# CON_SPDIF_IN.net
KiCad netlist of a schematic drawn in Altium Designer
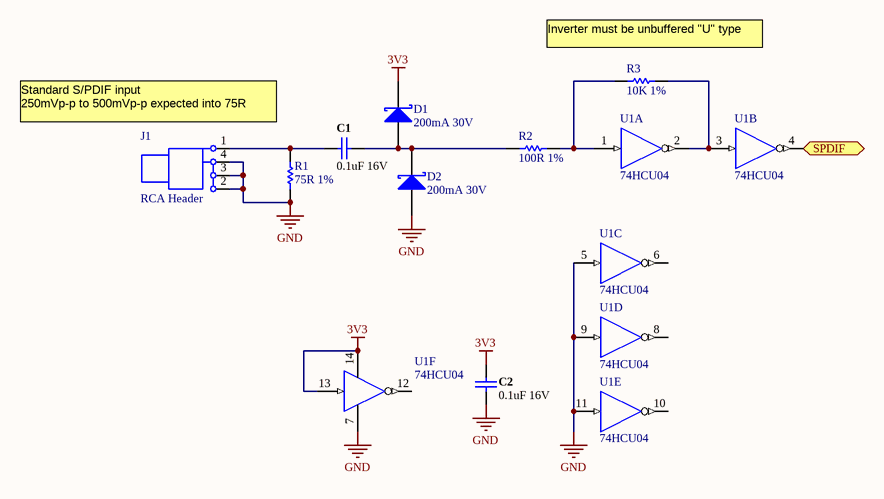
[diagram p0: CON_SPDIF_IN.SchDoc]

(export (version "E")
  (design (tool "Eeschema 10.0.6"))
  (components
    (comp (ref "C1")
      (value "0.1uF 16V")
      (footprint "CAPC1005-STAR")
      (description "Capacitor, Ceramic, 0.1uF 10% 16V 0402 (1005) X7R")
      (fields (field (name "TOLERANCE") "10 %"))
      (libsource (lib "AltiumDesignLibrary") (part "CAP-NP"))
    )
    (comp (ref "C2")
      (value "0.1uF 16V")
      (footprint "CAPC1005-STAR")
      (description "Capacitor, Ceramic, 0.1uF 10% 16V 0402 (1005) X7R")
      (fields (field (name "TOLERANCE") "10 %"))
      (libsource (lib "") (part "CAP-NP_1"))
    )
    (comp (ref "D1")
      (value "200mA 30V")
      (footprint "SOT95P230-3C")
      (description "Schottky Diode, BAT54 30V 200mA 30V SOT-23")
      (libsource (lib "AltiumDesignLibrary") (part "DIO-SCHOTTKY-1S-SOT23"))
    )
    (comp (ref "D2")
      (value "200mA 30V")
      (footprint "SOT95P230-3C")
      (description "Schottky Diode, BAT54 30V 200mA 30V SOT-23")
      (libsource (lib "AltiumDesignLibrary") (part "DIO-SCHOTTKY-1S-SOT23"))
    )
    (comp (ref "J1")
      (value "RCA Header")
      (footprint "TRC-005")
      (description "Connector, TRC-005-4 , RCA Phono Jack, Right Angle, Thru-Hole, Snap-In")
      (libsource (lib "AltiumDesignLibrary") (part "CON-RCA-RA"))
    )
    (comp (ref "R1")
      (value "75R 1%")
      (footprint "RESC1005-STAR")
      (description "Resistor, 75R 1% 0402")
      (fields (field (name "TOLERANCE") "1 %"))
      (libsource (lib "AltiumDesignLibrary") (part "RES"))
    )
    (comp (ref "R2")
      (value "100R 1%")
      (footprint "RESC1005-STAR")
      (description "Resistor, 100R 1% 0402 (1005)")
      (fields (field (name "TOLERANCE") "1 %"))
      (libsource (lib "AltiumDesignLibrary") (part "RES"))
    )
    (comp (ref "R3")
      (value "10K 1%")
      (footprint "RESC1005-STAR")
      (description "Resistor, 10K 1% 0402 (1005)")
      (fields (field (name "TOLERANCE") "1 %"))
      (libsource (lib "AltiumDesignLibrary") (part "RES"))
    )
    (comp (ref "U1")
      (value "74HCU04")
      (footprint "SOIC127P600-14")
      (description "74HCU04, HEX Inverter, Unbuffered")
      (libsource (lib "AltiumDesignLibrary") (part "74xx04"))
    )
  )
  (nets
    (net (code "1") (name "/SPDIF") (class "Default")
      (node (ref "U1") (pin "4") (pinfunction "Y_4") (pintype "output"))
    )
    (net (code "2") (name "3V3") (class "Default")
      (node (ref "C2") (pin "2") (pinfunction "2_2") (pintype "passive"))
      (node (ref "D1") (pin "3") (pinfunction "k_3") (pintype "passive"))
      (node (ref "U1") (pin "13") (pinfunction "A_13") (pintype "input"))
      (node (ref "U1") (pin "14") (pinfunction "VCC_14") (pintype "power_in"))
    )
    (net (code "3") (name "GND") (class "Default")
      (node (ref "C2") (pin "1") (pinfunction "1_1") (pintype "passive"))
      (node (ref "D2") (pin "1") (pinfunction "A_1") (pintype "passive"))
      (node (ref "J1") (pin "2") (pinfunction "Yellow_2") (pintype "passive"))
      (node (ref "J1") (pin "3") (pinfunction "White_3") (pintype "passive"))
      (node (ref "J1") (pin "4") (pinfunction "Red_4") (pintype "passive"))
      (node (ref "R1") (pin "2") (pinfunction "2_2") (pintype "passive"))
      (node (ref "U1") (pin "11") (pinfunction "A_11") (pintype "input"))
      (node (ref "U1") (pin "5") (pinfunction "A_5") (pintype "input"))
      (node (ref "U1") (pin "7") (pinfunction "GND_7") (pintype "power_in"))
      (node (ref "U1") (pin "9") (pinfunction "A_9") (pintype "input"))
    )
    (net (code "4") (name "Net-(D1-A)") (class "Default")
      (node (ref "C1") (pin "2") (pinfunction "2_2") (pintype "passive"))
      (node (ref "D1") (pin "1") (pinfunction "A_1") (pintype "passive"))
      (node (ref "D2") (pin "3") (pinfunction "k_3") (pintype "passive"))
      (node (ref "R2") (pin "2") (pinfunction "2_2") (pintype "passive"))
    )
    (net (code "5") (name "Net-(J1-Black)") (class "Default")
      (node (ref "C1") (pin "1") (pinfunction "1_1") (pintype "passive"))
      (node (ref "J1") (pin "1") (pinfunction "Black_1") (pintype "passive"))
      (node (ref "R1") (pin "1") (pinfunction "1_1") (pintype "passive"))
    )
    (net (code "6") (name "Net-(U1A-A)") (class "Default")
      (node (ref "R2") (pin "1") (pinfunction "1_1") (pintype "passive"))
      (node (ref "R3") (pin "1") (pinfunction "1_1") (pintype "passive"))
      (node (ref "U1") (pin "1") (pinfunction "A_1") (pintype "input"))
    )
    (net (code "7") (name "Net-(U1A-Y)") (class "Default")
      (node (ref "R3") (pin "2") (pinfunction "2_2") (pintype "passive"))
      (node (ref "U1") (pin "2") (pinfunction "Y_2") (pintype "output"))
      (node (ref "U1") (pin "3") (pinfunction "A_3") (pintype "input"))
    )
    (net (code "8") (name "unconnected-(D1-Pad2)") (class "Default")
      (node (ref "D1") (pin "2") (pintype "passive"))
    )
    (net (code "9") (name "unconnected-(D2-Pad2)") (class "Default")
      (node (ref "D2") (pin "2") (pintype "passive"))
    )
    (net (code "10") (name "unconnected-(U1C-Y-Pad6)") (class "Default")
      (node (ref "U1") (pin "6") (pinfunction "Y_6") (pintype "output"))
    )
    (net (code "11") (name "unconnected-(U1D-Y-Pad8)") (class "Default")
      (node (ref "U1") (pin "8") (pinfunction "Y_8") (pintype "output"))
    )
    (net (code "12") (name "unconnected-(U1E-Y-Pad10)") (class "Default")
      (node (ref "U1") (pin "10") (pinfunction "Y_10") (pintype "output"))
    )
    (net (code "13") (name "unconnected-(U1F-Y-Pad12)") (class "Default")
      (node (ref "U1") (pin "12") (pinfunction "Y_12") (pintype "output"))
    )
  )
)
